# opamp_prototype1.net
KiCad netlist of a schematic drawn in EAGLE
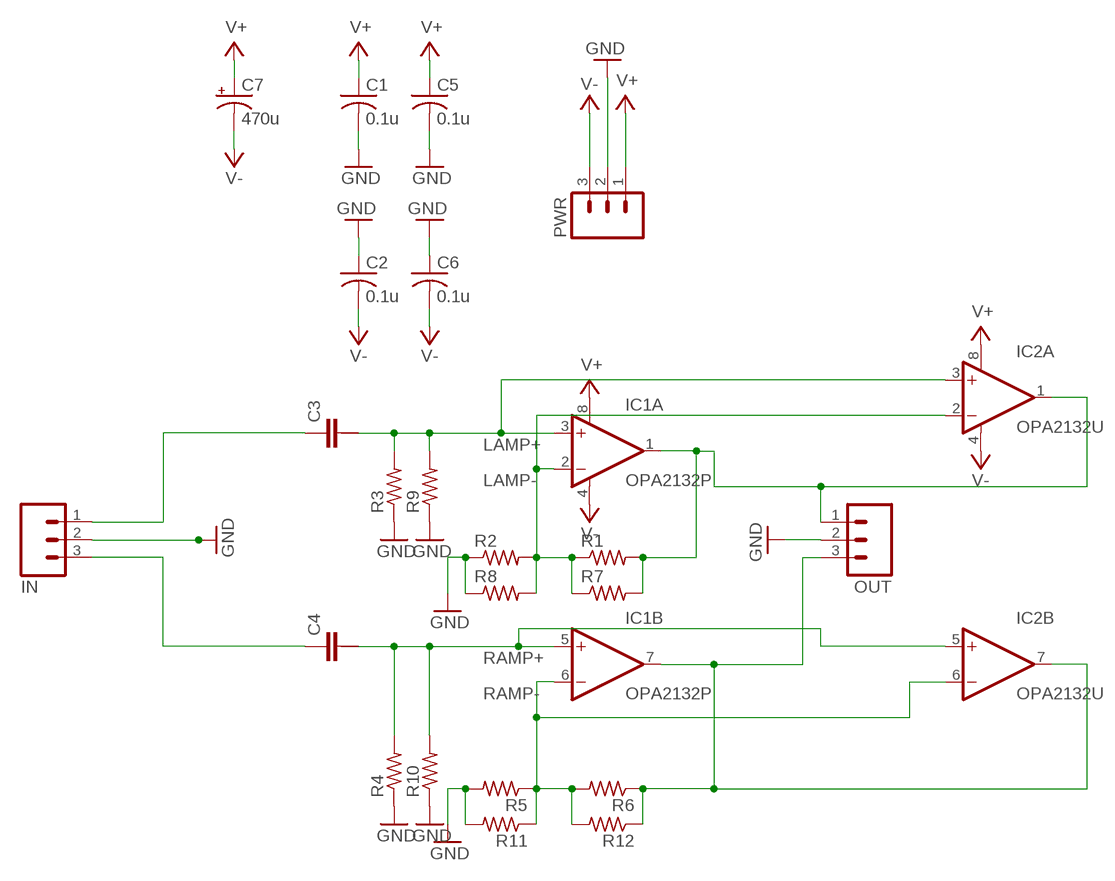
[diagram p0: schematic, sheet 1]

(export (version "E")
  (design (tool "Eeschema 10.0.6"))
  (components
    (comp (ref "C1")
      (value "0.1u")
      (footprint "eagle-import:C0805K")
      (libsource (lib "eagle-import") (part "C-USC0805K"))
    )
    (comp (ref "C2")
      (value "0.1u")
      (footprint "eagle-import:C0805K")
      (libsource (lib "eagle-import") (part "C-USC0805K"))
    )
    (comp (ref "C3")
      (value "C-2.5-5/6")
      (footprint "eagle-import:C2.5_5-6")
      (libsource (lib "eagle-import") (part "C-2.5-5/6"))
    )
    (comp (ref "C4")
      (value "C-2.5-5/6")
      (footprint "eagle-import:C2.5_5-6")
      (libsource (lib "eagle-import") (part "C-2.5-5/6"))
    )
    (comp (ref "C5")
      (value "0.1u")
      (footprint "eagle-import:C0805K")
      (libsource (lib "eagle-import") (part "C-USC0805K"))
    )
    (comp (ref "C6")
      (value "0.1u")
      (footprint "eagle-import:C0805K")
      (libsource (lib "eagle-import") (part "C-USC0805K"))
    )
    (comp (ref "C7")
      (value "470u")
      (footprint "eagle-import:CPOL-RADIAL-1000UF-25V")
      (libsource (lib "eagle-import") (part "CAP_POLPTH4"))
    )
    (comp (ref "IC1")
      (value "OPA2132P")
      (footprint "eagle-import:DIL08")
      (libsource (lib "eagle-import") (part "OPA2132P"))
    )
    (comp (ref "IC2")
      (value "OPA2132U")
      (footprint "eagle-import:SO08")
      (fields (field (name "MF") "TEXAS INSTRUMENTS"))
      (libsource (lib "eagle-import") (part "OPA2132U"))
    )
    (comp (ref "IN")
      (value "M03PTH")
      (footprint "eagle-import:1X03")
      (libsource (lib "eagle-import") (part "M03PTH"))
    )
    (comp (ref "OUT")
      (value "M03PTH")
      (footprint "eagle-import:1X03")
      (libsource (lib "eagle-import") (part "M03PTH"))
    )
    (comp (ref "PWR")
      (value "M03PTH")
      (footprint "eagle-import:1X03")
      (libsource (lib "eagle-import") (part "M03PTH"))
    )
    (comp (ref "R1")
      (value "R-US_0207/10")
      (footprint "eagle-import:0207_10")
      (libsource (lib "eagle-import") (part "R-US_0207/10"))
    )
    (comp (ref "R2")
      (value "R-US_0207/10")
      (footprint "eagle-import:0207_10")
      (libsource (lib "eagle-import") (part "R-US_0207/10"))
    )
    (comp (ref "R3")
      (value "R-US_0207/10")
      (footprint "eagle-import:0207_10")
      (libsource (lib "eagle-import") (part "R-US_0207/10"))
    )
    (comp (ref "R4")
      (value "R-US_0207/10")
      (footprint "eagle-import:0207_10")
      (libsource (lib "eagle-import") (part "R-US_0207/10"))
    )
    (comp (ref "R5")
      (value "R-US_0207/10")
      (footprint "eagle-import:0207_10")
      (libsource (lib "eagle-import") (part "R-US_0207/10"))
    )
    (comp (ref "R6")
      (value "R-US_0207/10")
      (footprint "eagle-import:0207_10")
      (libsource (lib "eagle-import") (part "R-US_0207/10"))
    )
    (comp (ref "R7")
      (value "R-US_R1206")
      (footprint "eagle-import:R1206")
      (libsource (lib "eagle-import") (part "rcl_R-US_R1206"))
    )
    (comp (ref "R8")
      (value "R-US_R1206")
      (footprint "eagle-import:R1206")
      (libsource (lib "eagle-import") (part "rcl_R-US_R1206"))
    )
    (comp (ref "R9")
      (value "R-US_R1206")
      (footprint "eagle-import:R1206")
      (libsource (lib "eagle-import") (part "rcl_R-US_R1206"))
    )
    (comp (ref "R10")
      (value "R-US_R1206")
      (footprint "eagle-import:R1206")
      (libsource (lib "eagle-import") (part "rcl_R-US_R1206"))
    )
    (comp (ref "R11")
      (value "R-US_R1206")
      (footprint "eagle-import:R1206")
      (libsource (lib "eagle-import") (part "rcl_R-US_R1206"))
    )
    (comp (ref "R12")
      (value "R-US_R1206")
      (footprint "eagle-import:R1206")
      (libsource (lib "eagle-import") (part "rcl_R-US_R1206"))
    )
  )
  (nets
    (net (code "1") (name "/LAMP+") (class "Default")
      (node (ref "C3") (pin "2") (pinfunction "2_2") (pintype "passive"))
      (node (ref "IC1") (pin "3") (pinfunction "+IN_3") (pintype "input"))
      (node (ref "IC2") (pin "3") (pinfunction "+IN_3") (pintype "input"))
      (node (ref "R3") (pin "2") (pinfunction "2_2") (pintype "passive"))
      (node (ref "R9") (pin "2") (pinfunction "2_2") (pintype "passive"))
    )
    (net (code "2") (name "/LAMP-") (class "Default")
      (node (ref "IC1") (pin "2") (pinfunction "-IN_2") (pintype "input"))
      (node (ref "IC2") (pin "2") (pinfunction "-IN_2") (pintype "input"))
      (node (ref "R1") (pin "1") (pinfunction "1_1") (pintype "passive"))
      (node (ref "R2") (pin "2") (pinfunction "2_2") (pintype "passive"))
      (node (ref "R7") (pin "1") (pinfunction "1_1") (pintype "passive"))
      (node (ref "R8") (pin "2") (pinfunction "2_2") (pintype "passive"))
    )
    (net (code "3") (name "/RAMP+") (class "Default")
      (node (ref "C4") (pin "2") (pinfunction "2_2") (pintype "passive"))
      (node (ref "IC1") (pin "5") (pinfunction "+IN_5") (pintype "input"))
      (node (ref "IC2") (pin "5") (pinfunction "+IN_5") (pintype "input"))
      (node (ref "R10") (pin "2") (pinfunction "2_2") (pintype "passive"))
      (node (ref "R4") (pin "2") (pinfunction "2_2") (pintype "passive"))
    )
    (net (code "4") (name "/RAMP-") (class "Default")
      (node (ref "IC1") (pin "6") (pinfunction "-IN_6") (pintype "input"))
      (node (ref "IC2") (pin "6") (pinfunction "-IN_6") (pintype "input"))
      (node (ref "R11") (pin "1") (pinfunction "1_1") (pintype "passive"))
      (node (ref "R12") (pin "2") (pinfunction "2_2") (pintype "passive"))
      (node (ref "R5") (pin "1") (pinfunction "1_1") (pintype "passive"))
      (node (ref "R6") (pin "2") (pinfunction "2_2") (pintype "passive"))
    )
    (net (code "5") (name "GND") (class "Default")
      (node (ref "C1") (pin "2") (pinfunction "2_2") (pintype "passive"))
      (node (ref "C2") (pin "1") (pinfunction "1_1") (pintype "passive"))
      (node (ref "C5") (pin "2") (pinfunction "2_2") (pintype "passive"))
      (node (ref "C6") (pin "1") (pinfunction "1_1") (pintype "passive"))
      (node (ref "IN") (pin "2") (pinfunction "2_2") (pintype "passive"))
      (node (ref "OUT") (pin "2") (pinfunction "2_2") (pintype "passive"))
      (node (ref "PWR") (pin "2") (pinfunction "2_2") (pintype "passive"))
      (node (ref "R10") (pin "1") (pinfunction "1_1") (pintype "passive"))
      (node (ref "R11") (pin "2") (pinfunction "2_2") (pintype "passive"))
      (node (ref "R2") (pin "1") (pinfunction "1_1") (pintype "passive"))
      (node (ref "R3") (pin "1") (pinfunction "1_1") (pintype "passive"))
      (node (ref "R4") (pin "1") (pinfunction "1_1") (pintype "passive"))
      (node (ref "R5") (pin "2") (pinfunction "2_2") (pintype "passive"))
      (node (ref "R8") (pin "1") (pinfunction "1_1") (pintype "passive"))
      (node (ref "R9") (pin "1") (pinfunction "1_1") (pintype "passive"))
    )
    (net (code "6") (name "Net-(C3-Pad1)") (class "Default")
      (node (ref "C3") (pin "1") (pinfunction "1_1") (pintype "passive"))
      (node (ref "IN") (pin "1") (pinfunction "1_1") (pintype "passive"))
    )
    (net (code "7") (name "Net-(C4-Pad1)") (class "Default")
      (node (ref "C4") (pin "1") (pinfunction "1_1") (pintype "passive"))
      (node (ref "IN") (pin "3") (pinfunction "3_3") (pintype "passive"))
    )
    (net (code "8") (name "Net-(IC1A-OUT)") (class "Default")
      (node (ref "IC1") (pin "1") (pinfunction "OUT_1") (pintype "output"))
      (node (ref "IC2") (pin "1") (pinfunction "OUT_1") (pintype "output"))
      (node (ref "OUT") (pin "1") (pinfunction "1_1") (pintype "passive"))
      (node (ref "R1") (pin "2") (pinfunction "2_2") (pintype "passive"))
      (node (ref "R7") (pin "2") (pinfunction "2_2") (pintype "passive"))
    )
    (net (code "9") (name "Net-(IC1B-OUT)") (class "Default")
      (node (ref "IC1") (pin "7") (pinfunction "OUT_7") (pintype "output"))
      (node (ref "IC2") (pin "7") (pinfunction "OUT_7") (pintype "output"))
      (node (ref "OUT") (pin "3") (pinfunction "3_3") (pintype "passive"))
      (node (ref "R12") (pin "1") (pinfunction "1_1") (pintype "passive"))
      (node (ref "R6") (pin "1") (pinfunction "1_1") (pintype "passive"))
    )
    (net (code "10") (name "V+") (class "Default")
      (node (ref "C1") (pin "1") (pinfunction "1_1") (pintype "passive"))
      (node (ref "C5") (pin "1") (pinfunction "1_1") (pintype "passive"))
      (node (ref "C7") (pin "+") (pinfunction "+_+") (pintype "passive"))
      (node (ref "IC1") (pin "8") (pinfunction "V+_8") (pintype "power_in"))
      (node (ref "IC2") (pin "8") (pinfunction "V+_8") (pintype "power_in"))
      (node (ref "PWR") (pin "1") (pinfunction "1_1") (pintype "passive"))
    )
    (net (code "11") (name "V-") (class "Default")
      (node (ref "C2") (pin "2") (pinfunction "2_2") (pintype "passive"))
      (node (ref "C6") (pin "2") (pinfunction "2_2") (pintype "passive"))
      (node (ref "C7") (pin "-") (pinfunction "-_-") (pintype "passive"))
      (node (ref "IC1") (pin "4") (pinfunction "V-_4") (pintype "power_in"))
      (node (ref "IC2") (pin "4") (pinfunction "V-_4") (pintype "power_in"))
      (node (ref "PWR") (pin "3") (pinfunction "3_3") (pintype "passive"))
    )
    (net (code "12") (name "unconnected-(C3-Pad3)") (class "Default")
      (node (ref "C3") (pin "3") (pinfunction "3_3") (pintype "passive"))
    )
    (net (code "13") (name "unconnected-(C4-Pad3)") (class "Default")
      (node (ref "C4") (pin "3") (pinfunction "3_3") (pintype "passive"))
    )
  )
)
